# charger-board.net
KiCad netlist of a schematic drawn in EAGLE
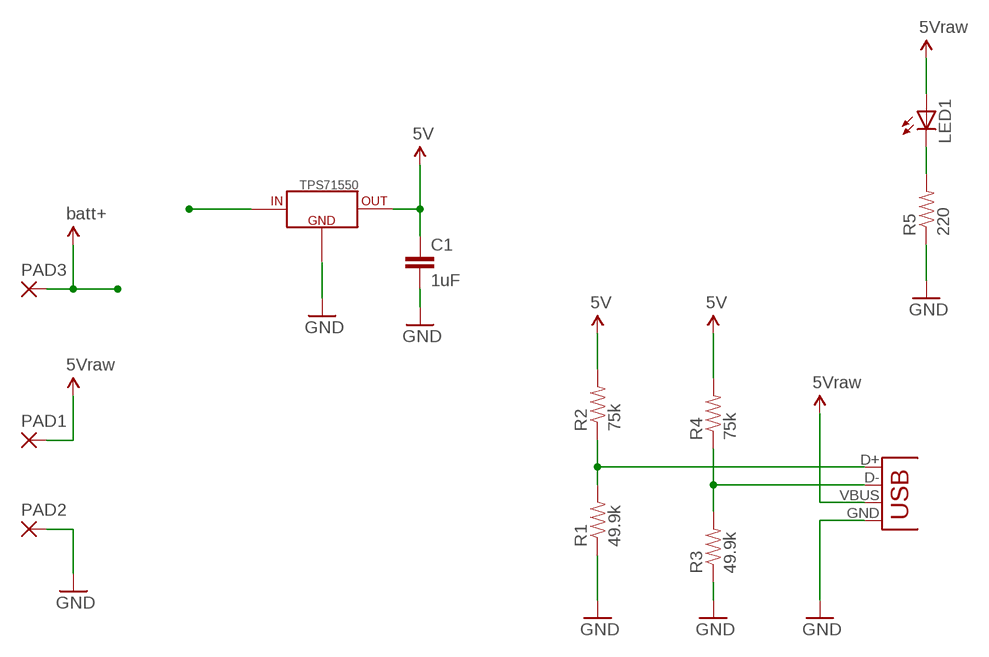
[diagram p0: schematic, sheet 1]

(export (version "E")
  (design (tool "Eeschema 10.0.6"))
  (components
    (comp (ref "C1")
      (value "1uF")
      (footprint "eagle-import:0805")
      (libsource (lib "eagle-import") (part "CAP0805"))
    )
    (comp (ref "JP1")
      (value "USB-A-S")
      (footprint "eagle-import:USB-A-S")
      (libsource (lib "eagle-import") (part "USB-A-S"))
    )
    (comp (ref "LED1")
      (value "LED0603")
      (footprint "eagle-import:LED-0603")
      (libsource (lib "eagle-import") (part "LED0603"))
    )
    (comp (ref "PAD1")
      (value "WIREPAD2,54/0,8")
      (footprint "eagle-import:2,54_0,8")
      (libsource (lib "eagle-import") (part "WIREPAD2,54/0,8"))
    )
    (comp (ref "PAD2")
      (value "WIREPAD2,54/0,8")
      (footprint "eagle-import:2,54_0,8")
      (libsource (lib "eagle-import") (part "WIREPAD2,54/0,8"))
    )
    (comp (ref "PAD3")
      (value "WIREPAD2,54/0,8")
      (footprint "eagle-import:2,54_0,8")
      (libsource (lib "eagle-import") (part "WIREPAD2,54/0,8"))
    )
    (comp (ref "R1")
      (value "49.9k")
      (footprint "eagle-import:0603-RES")
      (libsource (lib "eagle-import") (part "RESISTOR0603-RES"))
    )
    (comp (ref "R2")
      (value "75k")
      (footprint "eagle-import:0603-RES")
      (libsource (lib "eagle-import") (part "RESISTOR0603-RES"))
    )
    (comp (ref "R3")
      (value "49.9k")
      (footprint "eagle-import:0603-RES")
      (libsource (lib "eagle-import") (part "RESISTOR0603-RES"))
    )
    (comp (ref "R4")
      (value "75k")
      (footprint "eagle-import:0603-RES")
      (libsource (lib "eagle-import") (part "RESISTOR0603-RES"))
    )
    (comp (ref "R5")
      (value "220")
      (footprint "eagle-import:0603-RES")
      (libsource (lib "eagle-import") (part "RESISTOR0603-RES"))
    )
    (comp (ref "TPS71550")
      (value "TPS715XX")
      (footprint "eagle-import:SC70-5")
      (libsource (lib "eagle-import") (part "TPS715XX"))
    )
  )
  (nets
    (net (code "1") (name "5V") (class "Default")
      (node (ref "C1") (pin "1") (pinfunction "1_1") (pintype "passive"))
      (node (ref "R2") (pin "2") (pinfunction "2_2") (pintype "passive"))
      (node (ref "R4") (pin "2") (pinfunction "2_2") (pintype "passive"))
      (node (ref "TPS71550") (pin "5") (pinfunction "OUT_5") (pintype "bidirectional"))
    )
    (net (code "2") (name "5Vraw") (class "Default")
      (node (ref "JP1") (pin "VBUS") (pinfunction "VBUS_VBUS") (pintype "bidirectional"))
      (node (ref "LED1") (pin "A") (pinfunction "A_A") (pintype "passive"))
      (node (ref "PAD1") (pin "1") (pinfunction "P_1") (pintype "passive"))
    )
    (net (code "3") (name "GND") (class "Default")
      (node (ref "C1") (pin "2") (pinfunction "2_2") (pintype "passive"))
      (node (ref "JP1") (pin "GND") (pinfunction "GND_GND") (pintype "bidirectional"))
      (node (ref "PAD2") (pin "1") (pinfunction "P_1") (pintype "passive"))
      (node (ref "R1") (pin "1") (pinfunction "1_1") (pintype "passive"))
      (node (ref "R3") (pin "1") (pinfunction "1_1") (pintype "passive"))
      (node (ref "R5") (pin "1") (pinfunction "1_1") (pintype "passive"))
      (node (ref "TPS71550") (pin "2") (pinfunction "GND_2") (pintype "bidirectional"))
    )
    (net (code "4") (name "Net-(JP1-PadD+)") (class "Default")
      (node (ref "JP1") (pin "D+") (pinfunction "D+_D+") (pintype "bidirectional"))
      (node (ref "R1") (pin "2") (pinfunction "2_2") (pintype "passive"))
      (node (ref "R2") (pin "1") (pinfunction "1_1") (pintype "passive"))
    )
    (net (code "5") (name "Net-(JP1-PadD-)") (class "Default")
      (node (ref "JP1") (pin "D-") (pinfunction "D-_D-") (pintype "bidirectional"))
      (node (ref "R3") (pin "2") (pinfunction "2_2") (pintype "passive"))
      (node (ref "R4") (pin "1") (pinfunction "1_1") (pintype "passive"))
    )
    (net (code "6") (name "Net-(LED1-PadC)") (class "Default")
      (node (ref "LED1") (pin "C") (pinfunction "C_C") (pintype "passive"))
      (node (ref "R5") (pin "2") (pinfunction "2_2") (pintype "passive"))
    )
    (net (code "7") (name "batt+") (class "Default")
      (node (ref "PAD3") (pin "1") (pinfunction "P_1") (pintype "passive"))
      (node (ref "TPS71550") (pin "4") (pinfunction "IN_4") (pintype "bidirectional"))
    )
  )
)
